# SCFschem.net
KiCad netlist of a schematic drawn in EAGLE
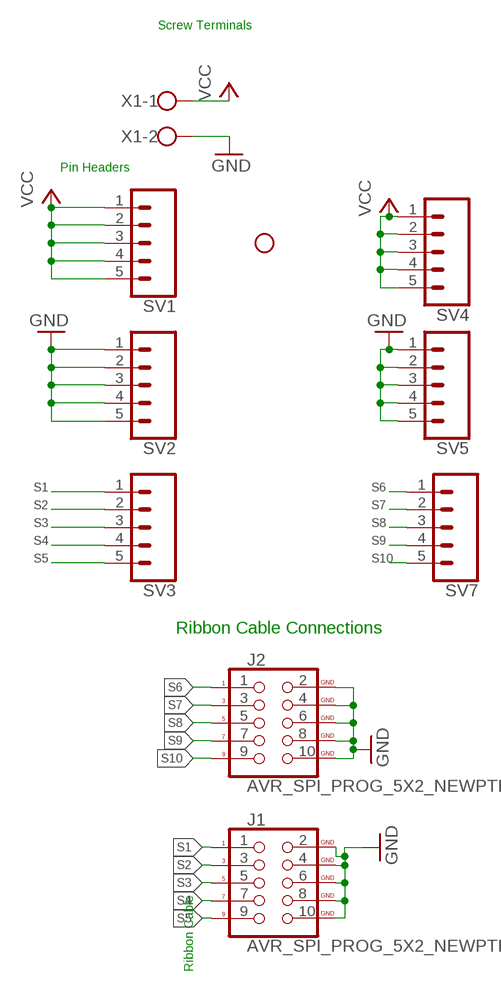
[diagram p0: schematic, sheet 1]

(export (version "E")
  (design (tool "Eeschema 10.0.6"))
  (components
    (comp (ref "H1")
      (value "STAND-OFF")
      (footprint "eagle-import:STAND-OFF")
      (libsource (lib "eagle-import") (part "STAND-OFF"))
    )
    (comp (ref "J1")
      (value "AVR_SPI_PROG_5X2_NEWPTH2")
      (footprint "eagle-import:2X5-SHROUDED")
      (libsource (lib "eagle-import") (part "AVR_SPI_PROG_5X2_NEWPTH2"))
    )
    (comp (ref "J2")
      (value "AVR_SPI_PROG_5X2_NEWPTH2")
      (footprint "eagle-import:2X5-SHROUDED")
      (libsource (lib "eagle-import") (part "AVR_SPI_PROG_5X2_NEWPTH2"))
    )
    (comp (ref "SV1")
      (value "CONN_05")
      (footprint "eagle-import:1X05")
      (libsource (lib "eagle-import") (part "CONN_05"))
    )
    (comp (ref "SV2")
      (value "CONN_05")
      (footprint "eagle-import:1X05")
      (libsource (lib "eagle-import") (part "CONN_05"))
    )
    (comp (ref "SV3")
      (value "CONN_05")
      (footprint "eagle-import:1X05")
      (libsource (lib "eagle-import") (part "CONN_05"))
    )
    (comp (ref "SV4")
      (value "CONN_05")
      (footprint "eagle-import:1X05")
      (libsource (lib "eagle-import") (part "CONN_05"))
    )
    (comp (ref "SV5")
      (value "CONN_05")
      (footprint "eagle-import:1X05")
      (libsource (lib "eagle-import") (part "CONN_05"))
    )
    (comp (ref "SV7")
      (value "CONN_05")
      (footprint "eagle-import:1X05")
      (libsource (lib "eagle-import") (part "CONN_05"))
    )
    (comp (ref "X1")
      (value "1X02_5MM_SCREW")
      (footprint "eagle-import:W237-102")
      (fields (field (name "MPN") "237-102"))
      (libsource (lib "eagle-import") (part "1X02_5MM_SCREW"))
    )
  )
  (nets
    (net (code "1") (name "GND") (class "Default")
      (node (ref "J1") (pin "10") (pinfunction "GND_10") (pintype "power_in"))
      (node (ref "J1") (pin "2") (pinfunction "GND_2") (pintype "power_in"))
      (node (ref "J1") (pin "4") (pinfunction "GND_4") (pintype "power_in"))
      (node (ref "J1") (pin "6") (pinfunction "GND_6") (pintype "power_in"))
      (node (ref "J1") (pin "8") (pinfunction "GND_8") (pintype "power_in"))
      (node (ref "J2") (pin "10") (pinfunction "GND_10") (pintype "power_in"))
      (node (ref "J2") (pin "2") (pinfunction "GND_2") (pintype "power_in"))
      (node (ref "J2") (pin "4") (pinfunction "GND_4") (pintype "power_in"))
      (node (ref "J2") (pin "6") (pinfunction "GND_6") (pintype "power_in"))
      (node (ref "J2") (pin "8") (pinfunction "GND_8") (pintype "power_in"))
      (node (ref "SV2") (pin "1") (pinfunction "1_1") (pintype "passive"))
      (node (ref "SV2") (pin "2") (pinfunction "2_2") (pintype "passive"))
      (node (ref "SV2") (pin "3") (pinfunction "3_3") (pintype "passive"))
      (node (ref "SV2") (pin "4") (pinfunction "4_4") (pintype "passive"))
      (node (ref "SV2") (pin "5") (pinfunction "5_5") (pintype "passive"))
      (node (ref "SV5") (pin "1") (pinfunction "1_1") (pintype "passive"))
      (node (ref "SV5") (pin "2") (pinfunction "2_2") (pintype "passive"))
      (node (ref "SV5") (pin "3") (pinfunction "3_3") (pintype "passive"))
      (node (ref "SV5") (pin "4") (pinfunction "4_4") (pintype "passive"))
      (node (ref "SV5") (pin "5") (pinfunction "5_5") (pintype "passive"))
      (node (ref "X1") (pin "2") (pinfunction "KL_2") (pintype "passive"))
    )
    (net (code "2") (name "S1") (class "Default")
      (node (ref "J1") (pin "1") (pinfunction "1_1") (pintype "passive"))
      (node (ref "SV3") (pin "1") (pinfunction "1_1") (pintype "passive"))
    )
    (net (code "3") (name "S2") (class "Default")
      (node (ref "J1") (pin "3") (pinfunction "3_3") (pintype "passive"))
      (node (ref "SV3") (pin "2") (pinfunction "2_2") (pintype "passive"))
    )
    (net (code "4") (name "S3") (class "Default")
      (node (ref "J1") (pin "5") (pinfunction "5_5") (pintype "passive"))
      (node (ref "SV3") (pin "3") (pinfunction "3_3") (pintype "passive"))
    )
    (net (code "5") (name "S4") (class "Default")
      (node (ref "J1") (pin "7") (pinfunction "7_7") (pintype "passive"))
      (node (ref "SV3") (pin "4") (pinfunction "4_4") (pintype "passive"))
    )
    (net (code "6") (name "S5") (class "Default")
      (node (ref "J1") (pin "9") (pinfunction "9_9") (pintype "passive"))
      (node (ref "SV3") (pin "5") (pinfunction "5_5") (pintype "passive"))
    )
    (net (code "7") (name "S6") (class "Default")
      (node (ref "J2") (pin "1") (pinfunction "1_1") (pintype "passive"))
      (node (ref "SV7") (pin "1") (pinfunction "1_1") (pintype "passive"))
    )
    (net (code "8") (name "S7") (class "Default")
      (node (ref "J2") (pin "3") (pinfunction "3_3") (pintype "passive"))
      (node (ref "SV7") (pin "2") (pinfunction "2_2") (pintype "passive"))
    )
    (net (code "9") (name "S8") (class "Default")
      (node (ref "J2") (pin "5") (pinfunction "5_5") (pintype "passive"))
      (node (ref "SV7") (pin "3") (pinfunction "3_3") (pintype "passive"))
    )
    (net (code "10") (name "S9") (class "Default")
      (node (ref "J2") (pin "7") (pinfunction "7_7") (pintype "passive"))
      (node (ref "SV7") (pin "4") (pinfunction "4_4") (pintype "passive"))
    )
    (net (code "11") (name "S10") (class "Default")
      (node (ref "J2") (pin "9") (pinfunction "9_9") (pintype "passive"))
      (node (ref "SV7") (pin "5") (pinfunction "5_5") (pintype "passive"))
    )
    (net (code "12") (name "VCC") (class "Default")
      (node (ref "SV1") (pin "1") (pinfunction "1_1") (pintype "passive"))
      (node (ref "SV1") (pin "2") (pinfunction "2_2") (pintype "passive"))
      (node (ref "SV1") (pin "3") (pinfunction "3_3") (pintype "passive"))
      (node (ref "SV1") (pin "4") (pinfunction "4_4") (pintype "passive"))
      (node (ref "SV1") (pin "5") (pinfunction "5_5") (pintype "passive"))
      (node (ref "SV4") (pin "1") (pinfunction "1_1") (pintype "passive"))
      (node (ref "SV4") (pin "2") (pinfunction "2_2") (pintype "passive"))
      (node (ref "SV4") (pin "3") (pinfunction "3_3") (pintype "passive"))
      (node (ref "SV4") (pin "4") (pinfunction "4_4") (pintype "passive"))
      (node (ref "SV4") (pin "5") (pinfunction "5_5") (pintype "passive"))
      (node (ref "X1") (pin "1") (pinfunction "KL_1") (pintype "passive"))
    )
  )
)
